# NP-100v12_cam.net
KiCad netlist of a schematic drawn in EAGLE
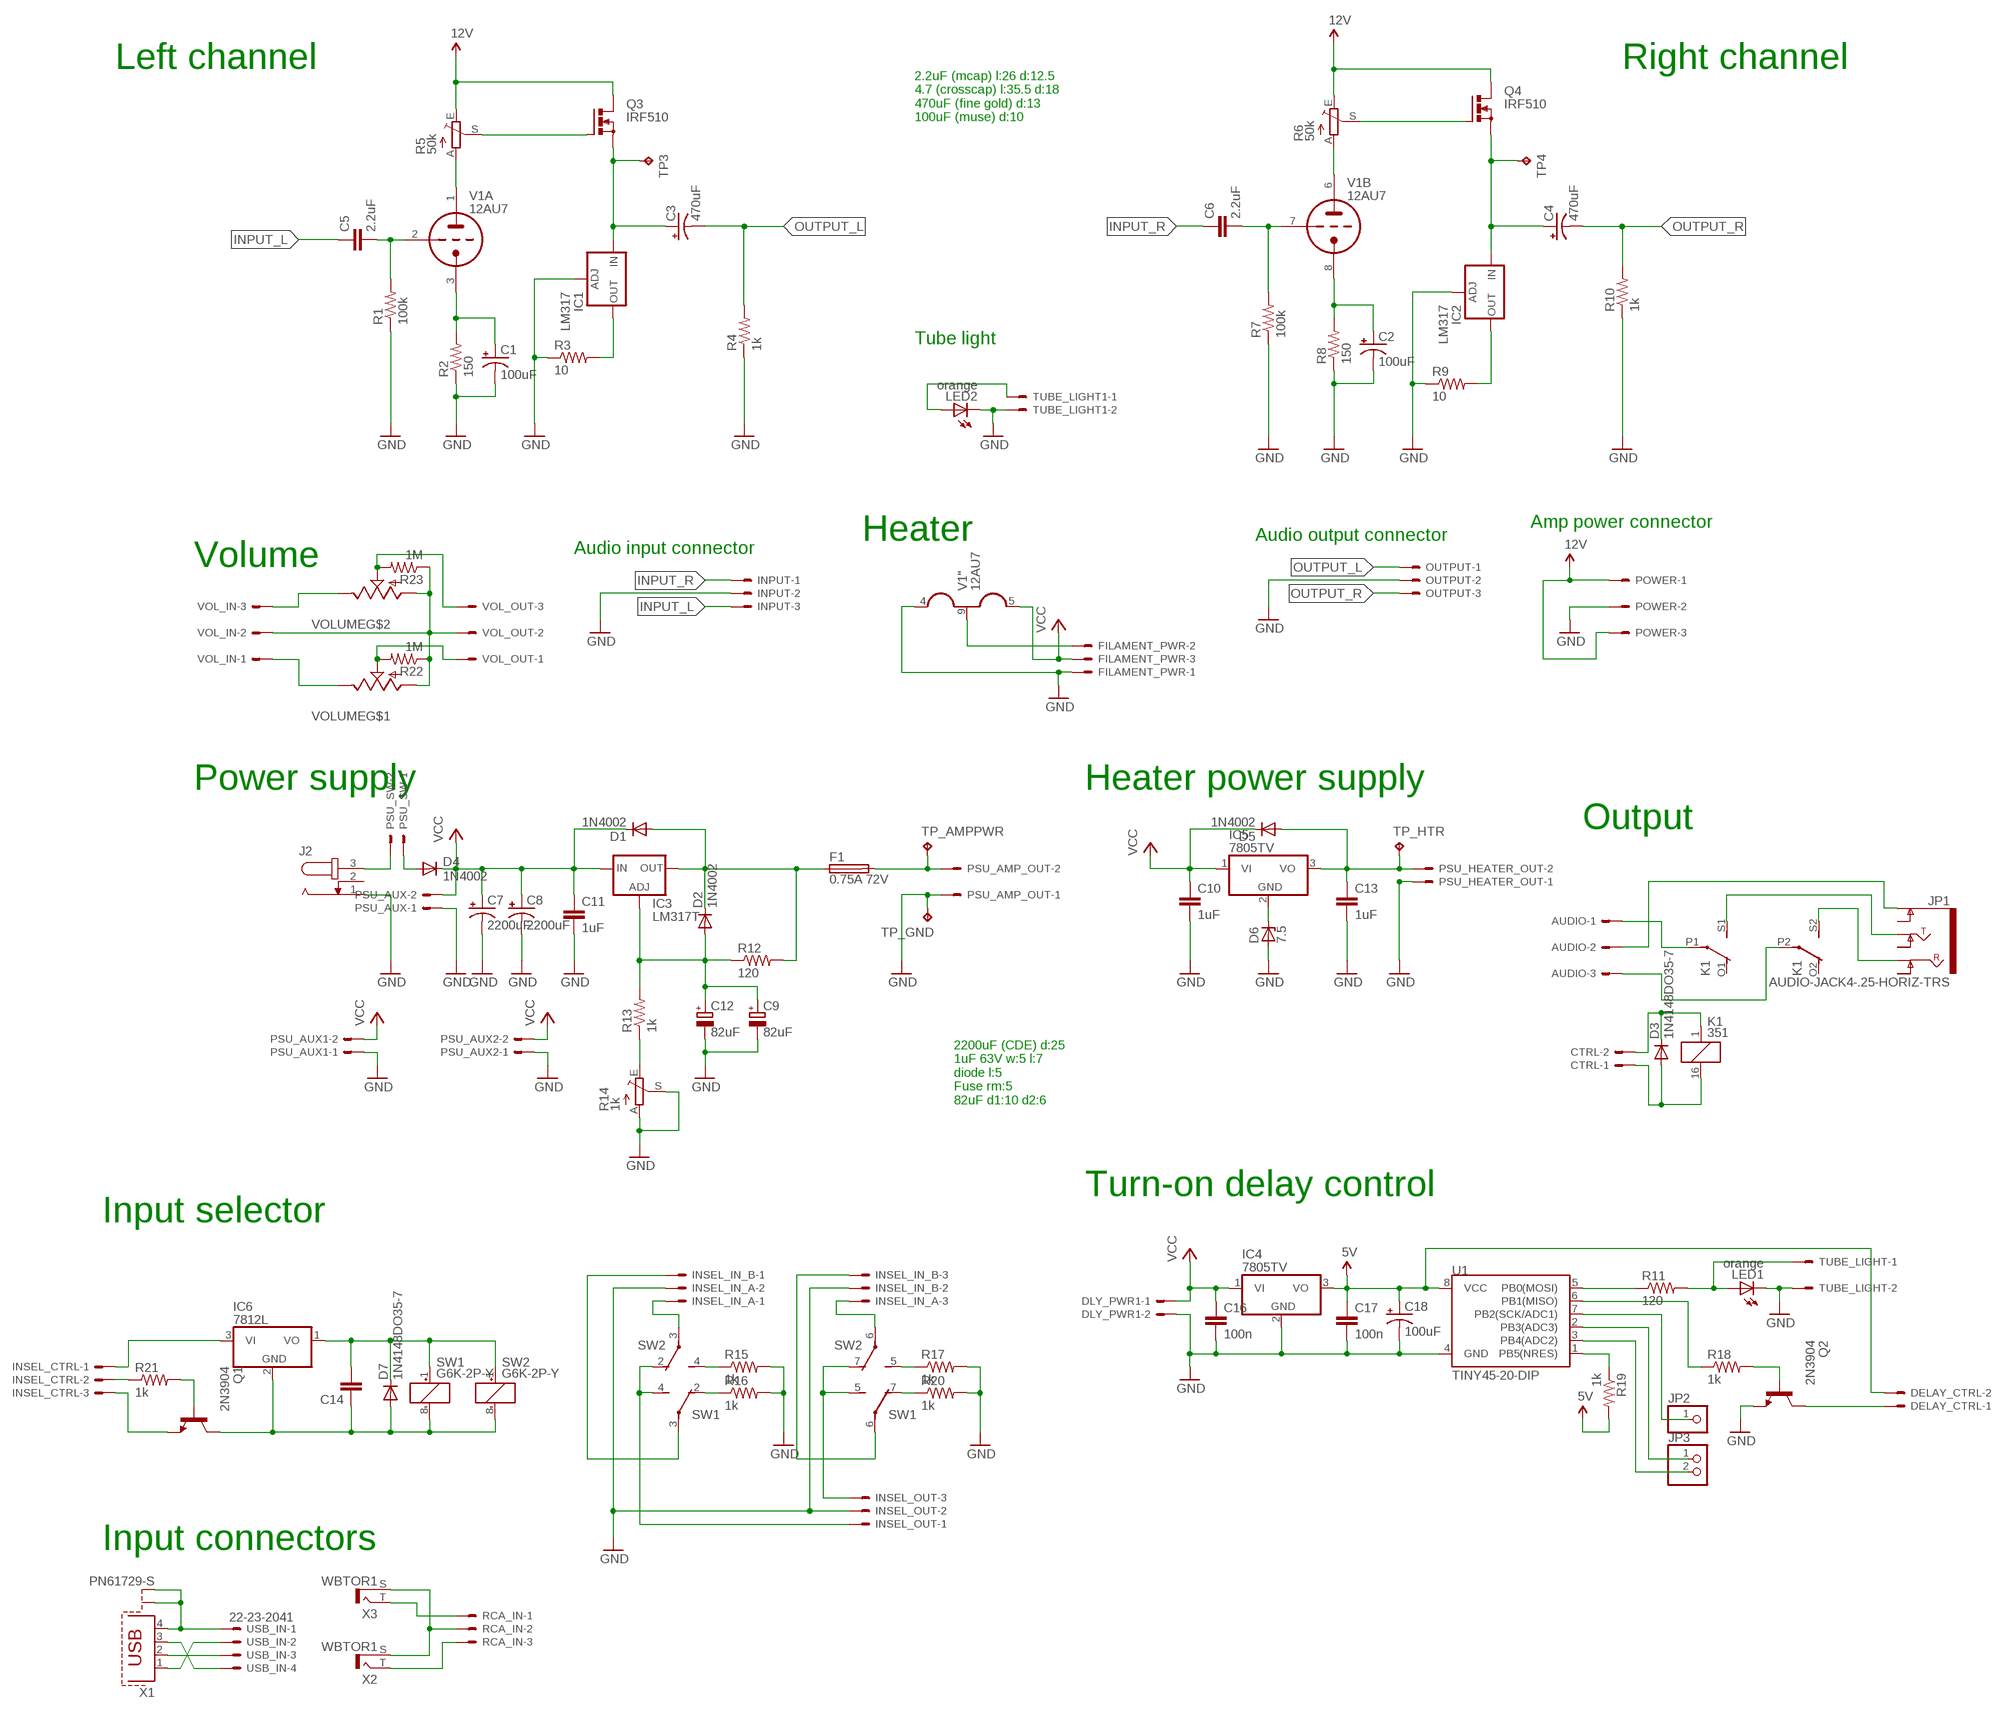
[diagram p0: schematic, sheet 1]

(export (version "E")
  (design (tool "Eeschema 10.0.6"))
  (components
    (comp (ref "AUDIO")
      (value "22-23-2031")
      (footprint "eagle-import:22-23-2031")
      (fields (field (name "MF") "MOLEX"))
      (libsource (lib "eagle-import") (part "22-23-2031"))
    )
    (comp (ref "C1")
      (value "100uF")
      (footprint "eagle-import:E5-10,5")
      (libsource (lib "eagle-import") (part "CPOL-USE5-10.5"))
    )
    (comp (ref "C2")
      (value "100uF")
      (footprint "eagle-import:E5-10,5")
      (libsource (lib "eagle-import") (part "CPOL-USE5-10.5"))
    )
    (comp (ref "C3")
      (value "470uF")
      (footprint "eagle-import:E5-13")
      (libsource (lib "eagle-import") (part "CPOL-USE5-13"))
    )
    (comp (ref "C4")
      (value "470uF")
      (footprint "eagle-import:E5-13")
      (libsource (lib "eagle-import") (part "CPOL-USE5-13"))
    )
    (comp (ref "C5")
      (value "2.2uF")
      (footprint "eagle-import:C37.5B19")
      (libsource (lib "eagle-import") (part "C37/19"))
    )
    (comp (ref "C6")
      (value "2.2uF")
      (footprint "eagle-import:C37.5B19")
      (libsource (lib "eagle-import") (part "C37/19"))
    )
    (comp (ref "C7")
      (value "2200uF")
      (footprint "eagle-import:EB25D")
      (libsource (lib "eagle-import") (part "CPOL-USE10-25"))
    )
    (comp (ref "C8")
      (value "2200uF")
      (footprint "eagle-import:EB25D")
      (libsource (lib "eagle-import") (part "CPOL-USE10-25"))
    )
    (comp (ref "C9")
      (value "82uF")
      (footprint "eagle-import:E2,5-6")
      (libsource (lib "eagle-import") (part "CPOL-EUE2.5-6"))
    )
    (comp (ref "C10")
      (value "1uF")
      (footprint "eagle-import:C5B4.5")
      (libsource (lib "eagle-import") (part "C5/4.5"))
    )
    (comp (ref "C11")
      (value "1uF")
      (footprint "eagle-import:C5B4.5")
      (libsource (lib "eagle-import") (part "C5/4.5"))
    )
    (comp (ref "C12")
      (value "82uF")
      (footprint "eagle-import:E5-10,5")
      (libsource (lib "eagle-import") (part "CPOL-EUE5-10.5"))
    )
    (comp (ref "C13")
      (value "1uF")
      (footprint "eagle-import:C5B4.5")
      (libsource (lib "eagle-import") (part "C5/4.5"))
    )
    (comp (ref "C14")
      (value "C5/2.5")
      (footprint "eagle-import:C5B2.5")
      (libsource (lib "eagle-import") (part "C5/2.5"))
    )
    (comp (ref "C16")
      (value "100n")
      (footprint "eagle-import:CAP-PTH-5MM")
      (libsource (lib "eagle-import") (part "CAPPTH1"))
    )
    (comp (ref "C17")
      (value "100n")
      (footprint "eagle-import:CAP-PTH-5MM")
      (libsource (lib "eagle-import") (part "CAPPTH1"))
    )
    (comp (ref "C18")
      (value "100uF")
      (footprint "eagle-import:E2,5-7")
      (libsource (lib "eagle-import") (part "CPOL-USE2.5-7"))
    )
    (comp (ref "CTRL")
      (value "22-23-2021")
      (footprint "eagle-import:22-23-2021")
      (fields (field (name "MF") "MOLEX"))
      (libsource (lib "eagle-import") (part "22-23-2021"))
    )
    (comp (ref "D1")
      (value "1N4002")
      (footprint "eagle-import:D-7.5")
      (libsource (lib "eagle-import") (part "DIODE-D-7.5"))
    )
    (comp (ref "D2")
      (value "1N4002")
      (footprint "eagle-import:D-7.5")
      (libsource (lib "eagle-import") (part "DIODE-D-7.5"))
    )
    (comp (ref "D3")
      (value "1N4148DO35-7")
      (footprint "eagle-import:DO35-7")
      (libsource (lib "eagle-import") (part "1N4148DO35-7"))
    )
    (comp (ref "D4")
      (value "1N4002")
      (footprint "eagle-import:D-5")
      (libsource (lib "eagle-import") (part "DIODE-D-5"))
    )
    (comp (ref "D5")
      (value "1N4002")
      (footprint "eagle-import:D-7.5")
      (libsource (lib "eagle-import") (part "DIODE-D-7.5"))
    )
    (comp (ref "D6")
      (value "7.5")
      (footprint "eagle-import:DO34Z7")
      (libsource (lib "eagle-import") (part "ZENER-DIODEDO34-7"))
    )
    (comp (ref "D7")
      (value "1N4148DO35-7")
      (footprint "eagle-import:DO35-7")
      (libsource (lib "eagle-import") (part "1N4148DO35-7"))
    )
    (comp (ref "DELAY_CTRL")
      (value "22-23-2021")
      (footprint "eagle-import:22-23-2021")
      (fields (field (name "MF") "MOLEX"))
      (libsource (lib "eagle-import") (part "22-23-2021"))
    )
    (comp (ref "DLY_PWR1")
      (value "22-23-2021")
      (footprint "eagle-import:22-23-2021")
      (fields (field (name "MF") "MOLEX"))
      (libsource (lib "eagle-import") (part "22-23-2021"))
    )
    (comp (ref "F1")
      (value "0.75A 72V")
      (footprint "eagle-import:TE5")
      (libsource (lib "eagle-import") (part "TE5"))
    )
    (comp (ref "FILAMENT_PWR")
      (value "22-23-2031")
      (footprint "eagle-import:22-23-2031")
      (fields (field (name "MF") "MOLEX"))
      (libsource (lib "eagle-import") (part "22-23-2031"))
    )
    (comp (ref "IC1")
      (value "LM317")
      (footprint "eagle-import:317TS")
      (libsource (lib "eagle-import") (part "LM317TS"))
    )
    (comp (ref "IC2")
      (value "LM317")
      (footprint "eagle-import:317TS")
      (libsource (lib "eagle-import") (part "LM317TS"))
    )
    (comp (ref "IC3")
      (value "LM317T")
      (footprint "eagle-import:317TS")
      (libsource (lib "eagle-import") (part "LM317TS"))
    )
    (comp (ref "IC4")
      (value "7805TV")
      (footprint "eagle-import:TO220V")
      (libsource (lib "eagle-import") (part "78TV05"))
    )
    (comp (ref "IC5")
      (value "7805TV")
      (footprint "eagle-import:TO220V")
      (libsource (lib "eagle-import") (part "78TV05"))
    )
    (comp (ref "IC6")
      (value "7812L")
      (footprint "eagle-import:TO92")
      (libsource (lib "eagle-import") (part "78L12"))
    )
    (comp (ref "INPUT")
      (value "22-23-2031")
      (footprint "eagle-import:22-23-2031")
      (fields (field (name "MF") "MOLEX"))
      (libsource (lib "eagle-import") (part "22-23-2031"))
    )
    (comp (ref "INSEL_CTRL")
      (value "22-23-2031")
      (footprint "eagle-import:22-23-2031")
      (fields (field (name "MF") "MOLEX"))
      (libsource (lib "eagle-import") (part "22-23-2031"))
    )
    (comp (ref "INSEL_IN_A")
      (value "22-23-2031")
      (footprint "eagle-import:22-23-2031")
      (fields (field (name "MF") "MOLEX"))
      (libsource (lib "eagle-import") (part "22-23-2031"))
    )
    (comp (ref "INSEL_IN_B")
      (value "22-23-2031")
      (footprint "eagle-import:22-23-2031")
      (fields (field (name "MF") "MOLEX"))
      (libsource (lib "eagle-import") (part "22-23-2031"))
    )
    (comp (ref "INSEL_OUT")
      (value "22-23-2031")
      (footprint "eagle-import:22-23-2031")
      (fields (field (name "MF") "MOLEX"))
      (libsource (lib "eagle-import") (part "22-23-2031"))
    )
    (comp (ref "J2")
      (value "JACK-PLUG0")
      (footprint "eagle-import:SPC4077")
      (libsource (lib "eagle-import") (part "JACK-PLUG0"))
    )
    (comp (ref "JP1")
      (value "AUDIO-JACK4-.25-HORIZ-TRS")
      (footprint "eagle-import:AUDIO-JACK-.25-INCH-HORIZ-PTH")
      (libsource (lib "eagle-import") (part "AUDIO-JACK4-.25-HORIZ-TRS"))
    )
    (comp (ref "JP2")
      (value "PINHD-1X1")
      (footprint "eagle-import:1X01")
      (libsource (lib "eagle-import") (part "PINHD-1X1"))
    )
    (comp (ref "JP3")
      (value "PINHD-1X2")
      (footprint "eagle-import:1X02")
      (libsource (lib "eagle-import") (part "PINHD-1X2"))
    )
    (comp (ref "K1")
      (value "351")
      (footprint "eagle-import:351")
      (libsource (lib "eagle-import") (part "351"))
    )
    (comp (ref "LED1")
      (value "orange")
      (footprint "eagle-import:LED3MM")
      (libsource (lib "eagle-import") (part "LED3MM"))
    )
    (comp (ref "LED2")
      (value "orange")
      (footprint "eagle-import:LED3MM")
      (libsource (lib "eagle-import") (part "LED3MM"))
    )
    (comp (ref "OUTPUT")
      (value "22-23-2031")
      (footprint "eagle-import:22-23-2031")
      (fields (field (name "MF") "MOLEX"))
      (libsource (lib "eagle-import") (part "22-23-2031"))
    )
    (comp (ref "POWER")
      (value "22-23-2031")
      (footprint "eagle-import:22-23-2031")
      (fields (field (name "MF") "MOLEX"))
      (libsource (lib "eagle-import") (part "22-23-2031"))
    )
    (comp (ref "PSU_AMP_OUT")
      (value "22-23-2021")
      (footprint "eagle-import:22-23-2021")
      (fields (field (name "MF") "MOLEX"))
      (libsource (lib "eagle-import") (part "22-23-2021"))
    )
    (comp (ref "PSU_AUX")
      (value "22-23-2021")
      (footprint "eagle-import:22-23-2021")
      (fields (field (name "MF") "MOLEX"))
      (libsource (lib "eagle-import") (part "22-23-2021"))
    )
    (comp (ref "PSU_AUX1")
      (value "22-23-2021")
      (footprint "eagle-import:22-23-2021")
      (fields (field (name "MF") "MOLEX"))
      (libsource (lib "eagle-import") (part "22-23-2021"))
    )
    (comp (ref "PSU_AUX2")
      (value "22-23-2021")
      (footprint "eagle-import:22-23-2021")
      (fields (field (name "MF") "MOLEX"))
      (libsource (lib "eagle-import") (part "22-23-2021"))
    )
    (comp (ref "PSU_HEATER_OUT")
      (value "22-23-2021")
      (footprint "eagle-import:22-23-2021")
      (fields (field (name "MF") "MOLEX"))
      (libsource (lib "eagle-import") (part "22-23-2021"))
    )
    (comp (ref "PSU_SW")
      (value "22-23-2021")
      (footprint "eagle-import:22-23-2021")
      (fields (field (name "MF") "MOLEX"))
      (libsource (lib "eagle-import") (part "22-23-2021"))
    )
    (comp (ref "Q1")
      (value "2N3904")
      (footprint "eagle-import:TO92")
      (libsource (lib "eagle-import") (part "2N3904"))
    )
    (comp (ref "Q2")
      (value "2N3904")
      (footprint "eagle-import:TO92")
      (libsource (lib "eagle-import") (part "2N3904"))
    )
    (comp (ref "Q3")
      (value "IRF510")
      (footprint "eagle-import:TO220BV")
      (libsource (lib "eagle-import") (part "PMOSFET_NTO220BV"))
    )
    (comp (ref "Q4")
      (value "IRF510")
      (footprint "eagle-import:TO220BV")
      (libsource (lib "eagle-import") (part "PMOSFET_NTO220BV"))
    )
    (comp (ref "R1")
      (value "100k")
      (footprint "eagle-import:0207_10")
      (libsource (lib "eagle-import") (part "R-US_0207/10"))
    )
    (comp (ref "R2")
      (value "150")
      (footprint "eagle-import:0207_10")
      (libsource (lib "eagle-import") (part "R-US_0207/10"))
    )
    (comp (ref "R3")
      (value "10")
      (footprint "eagle-import:0207_10")
      (libsource (lib "eagle-import") (part "R-US_0207/10"))
    )
    (comp (ref "R4")
      (value "1k")
      (footprint "eagle-import:0207_10")
      (libsource (lib "eagle-import") (part "R-US_0207/10"))
    )
    (comp (ref "R5")
      (value "50k")
      (footprint "eagle-import:SP19L")
      (libsource (lib "eagle-import") (part "TRIM_EU-B90P"))
    )
    (comp (ref "R6")
      (value "50k")
      (footprint "eagle-import:SP19L")
      (libsource (lib "eagle-import") (part "TRIM_EU-B90P"))
    )
    (comp (ref "R7")
      (value "100k")
      (footprint "eagle-import:0207_10")
      (libsource (lib "eagle-import") (part "R-US_0207/10"))
    )
    (comp (ref "R8")
      (value "150")
      (footprint "eagle-import:0207_10")
      (libsource (lib "eagle-import") (part "R-US_0207/10"))
    )
    (comp (ref "R9")
      (value "10")
      (footprint "eagle-import:0207_10")
      (libsource (lib "eagle-import") (part "R-US_0207/10"))
    )
    (comp (ref "R10")
      (value "1k")
      (footprint "eagle-import:0207_10")
      (libsource (lib "eagle-import") (part "R-US_0207/10"))
    )
    (comp (ref "R11")
      (value "120")
      (footprint "eagle-import:0204_7")
      (libsource (lib "eagle-import") (part "R-US_0204/7"))
    )
    (comp (ref "R12")
      (value "120")
      (footprint "eagle-import:AXIAL-0.3")
      (libsource (lib "eagle-import") (part "RESISTORAXIAL-0.3"))
    )
    (comp (ref "R13")
      (value "1k")
      (footprint "eagle-import:AXIAL-0.3")
      (libsource (lib "eagle-import") (part "RESISTORAXIAL-0.3"))
    )
    (comp (ref "R14")
      (value "1k")
      (footprint "eagle-import:S64Y")
      (libsource (lib "eagle-import") (part "TRIM_EU-S64Y"))
    )
    (comp (ref "R15")
      (value "1k")
      (footprint "eagle-import:AXIAL-0.3")
      (libsource (lib "eagle-import") (part "RESISTORAXIAL-0.3"))
    )
    (comp (ref "R16")
      (value "1k")
      (footprint "eagle-import:AXIAL-0.3")
      (libsource (lib "eagle-import") (part "RESISTORAXIAL-0.3"))
    )
    (comp (ref "R17")
      (value "1k")
      (footprint "eagle-import:AXIAL-0.3")
      (libsource (lib "eagle-import") (part "RESISTORAXIAL-0.3"))
    )
    (comp (ref "R18")
      (value "1k")
      (footprint "eagle-import:0204_7")
      (libsource (lib "eagle-import") (part "R-US_0204/7"))
    )
    (comp (ref "R19")
      (value "1k")
      (footprint "eagle-import:0204_7")
      (libsource (lib "eagle-import") (part "R-US_0204/7"))
    )
    (comp (ref "R20")
      (value "1k")
      (footprint "eagle-import:AXIAL-0.3")
      (libsource (lib "eagle-import") (part "RESISTORAXIAL-0.3"))
    )
    (comp (ref "R21")
      (value "1k")
      (footprint "eagle-import:0204_7")
      (libsource (lib "eagle-import") (part "R-US_0204/7"))
    )
    (comp (ref "R22")
      (value "1M")
      (footprint "eagle-import:0207_10")
      (libsource (lib "eagle-import") (part "R-US_0207/10"))
    )
    (comp (ref "R23")
      (value "1M")
      (footprint "eagle-import:0207_10")
      (libsource (lib "eagle-import") (part "R-US_0207/10"))
    )
    (comp (ref "RCA_IN")
      (value "22-23-2031")
      (footprint "eagle-import:22-23-2031")
      (fields (field (name "MF") "MOLEX"))
      (libsource (lib "eagle-import") (part "22-23-2031"))
    )
    (comp (ref "SW1")
      (value "G6K-2P-Y")
      (footprint "eagle-import:G6K-2P-Y")
      (fields (field (name "MF") "OMRON COMPONENTS USA") (field (name "MPN") "G6K-2P-Y DC12"))
      (libsource (lib "eagle-import") (part "G6K-2P-Y"))
    )
    (comp (ref "SW2")
      (value "G6K-2P-Y")
      (footprint "eagle-import:G6K-2P-Y")
      (fields (field (name "MF") "OMRON COMPONENTS USA") (field (name "MPN") "G6K-2P-Y DC12"))
      (libsource (lib "eagle-import") (part "G6K-2P-Y"))
    )
    (comp (ref "TP3")
      (value "TPPAD1-17")
      (footprint "eagle-import:P1-17")
      (libsource (lib "eagle-import") (part "TPPAD1-17"))
    )
    (comp (ref "TP4")
      (value "TPPAD1-17")
      (footprint "eagle-import:P1-17")
      (libsource (lib "eagle-import") (part "TPPAD1-17"))
    )
    (comp (ref "TP_AMPPWR")
      (value "TPPAD1-17")
      (footprint "eagle-import:P1-17")
      (libsource (lib "eagle-import") (part "TPPAD1-17"))
    )
    (comp (ref "TP_GND")
      (value "TPPAD1-17")
      (footprint "eagle-import:P1-17")
      (libsource (lib "eagle-import") (part "TPPAD1-17"))
    )
    (comp (ref "TP_HTR")
      (value "TPPAD1-17")
      (footprint "eagle-import:P1-17")
      (libsource (lib "eagle-import") (part "TPPAD1-17"))
    )
    (comp (ref "TUBE_LIGHT")
      (value "22-23-2021")
      (footprint "eagle-import:22-23-2021")
      (fields (field (name "MF") "MOLEX"))
      (libsource (lib "eagle-import") (part "22-23-2021"))
    )
    (comp (ref "TUBE_LIGHT1")
      (value "22-23-2021")
      (footprint "eagle-import:22-23-2021")
      (fields (field (name "MF") "MOLEX"))
      (libsource (lib "eagle-import") (part "22-23-2021"))
    )
    (comp (ref "U1")
      (value "TINY45-20-DIP")
      (footprint "eagle-import:DIP08")
      (libsource (lib "eagle-import") (part "ATTINY45TINY45-20-DIP"))
    )
    (comp (ref "USB_IN")
      (value "22-23-2041")
      (footprint "eagle-import:22-23-2041")
      (fields (field (name "MF") "MOLEX"))
      (libsource (lib "eagle-import") (part "22-23-2041"))
    )
    (comp (ref "V1")
      (value "12AU7")
      (footprint "eagle-import:NOVAL")
      (libsource (lib "eagle-import") (part "12AU7-P"))
    )
    (comp (ref "VOLUME")
      (value "ALPS_BLUE")
      (footprint "eagle-import:ALPS_RK27")
      (libsource (lib "eagle-import") (part "ALPS_BLUE"))
    )
    (comp (ref "VOL_IN")
      (value "22-23-2031")
      (footprint "eagle-import:22-23-2031")
      (fields (field (name "MF") "MOLEX"))
      (libsource (lib "eagle-import") (part "22-23-2031"))
    )
    (comp (ref "VOL_OUT")
      (value "22-23-2031")
      (footprint "eagle-import:22-23-2031")
      (fields (field (name "MF") "MOLEX"))
      (libsource (lib "eagle-import") (part "22-23-2031"))
    )
    (comp (ref "X1")
      (value "PN61729-S")
      (footprint "eagle-import:PN61729-S")
      (libsource (lib "eagle-import") (part "PN61729-S"))
    )
    (comp (ref "X2")
      (value "WBTOR1")
      (footprint "eagle-import:WBTOR1")
      (fields (field (name "MPN") "WBTOR 1 BLACK"))
      (libsource (lib "eagle-import") (part "WBTOR1"))
    )
    (comp (ref "X3")
      (value "WBTOR1")
      (footprint "eagle-import:WBTOR1")
      (fields (field (name "MPN") "WBTOR 1 BLACK"))
      (libsource (lib "eagle-import") (part "WBTOR1"))
    )
  )
  (nets
    (net (code "1") (name "5V") (class "Default")
      (node (ref "C17") (pin "1") (pinfunction "1_1") (pintype "passive"))
      (node (ref "C18") (pin "+") (pinfunction "+_+") (pintype "passive"))
      (node (ref "DELAY_CTRL") (pin "2") (pinfunction "S_2") (pintype "passive"))
      (node (ref "IC4") (pin "3") (pinfunction "VO_3") (pintype "passive"))
      (node (ref "R19") (pin "2") (pinfunction "2_2") (pintype "passive"))
      (node (ref "U1") (pin "8") (pinfunction "VCC_8") (pintype "bidirectional"))
    )
    (net (code "2") (name "12V") (class "Default")
      (node (ref "POWER") (pin "1") (pinfunction "S_1") (pintype "passive"))
      (node (ref "POWER") (pin "3") (pinfunction "S_3") (pintype "passive"))
      (node (ref "Q3") (pin "D") (pinfunction "D_D") (pintype "passive"))
      (node (ref "Q4") (pin "D") (pinfunction "D_D") (pintype "passive"))
      (node (ref "R5") (pin "E") (pinfunction "E_E") (pintype "passive"))
      (node (ref "R6") (pin "E") (pinfunction "E_E") (pintype "passive"))
    )
    (net (code "3") (name "GND") (class "Default")
      (node (ref "C1") (pin "-") (pinfunction "-_-") (pintype "passive"))
      (node (ref "C10") (pin "2") (pinfunction "2_2") (pintype "passive"))
      (node (ref "C11") (pin "2") (pinfunction "2_2") (pintype "passive"))
      (node (ref "C12") (pin "-") (pinfunction "-_-") (pintype "passive"))
      (node (ref "C13") (pin "2") (pinfunction "2_2") (pintype "passive"))
      (node (ref "C16") (pin "2") (pinfunction "2_2") (pintype "passive"))
      (node (ref "C17") (pin "2") (pinfunction "2_2") (pintype "passive"))
      (node (ref "C18") (pin "-") (pinfunction "-_-") (pintype "passive"))
      (node (ref "C2") (pin "-") (pinfunction "-_-") (pintype "passive"))
      (node (ref "C7") (pin "-") (pinfunction "-_-") (pintype "passive"))
      (node (ref "C8") (pin "-") (pinfunction "-_-") (pintype "passive"))
      (node (ref "C9") (pin "-") (pinfunction "-_-") (pintype "passive"))
      (node (ref "D6") (pin "A") (pinfunction "A_A") (pintype "passive"))
      (node (ref "DLY_PWR1") (pin "2") (pinfunction "S_2") (pintype "passive"))
      (node (ref "FILAMENT_PWR") (pin "1") (pinfunction "S_1") (pintype "passive"))
      (node (ref "IC1") (pin "1") (pinfunction "ADJ_1") (pintype "input"))
      (node (ref "IC2") (pin "1") (pinfunction "ADJ_1") (pintype "input"))
      (node (ref "IC4") (pin "2") (pinfunction "GND_2") (pintype "passive"))
      (node (ref "INPUT") (pin "2") (pinfunction "S_2") (pintype "passive"))
      (node (ref "INSEL_IN_A") (pin "2") (pinfunction "S_2") (pintype "passive"))
      (node (ref "INSEL_IN_B") (pin "2") (pinfunction "S_2") (pintype "passive"))
      (node (ref "INSEL_OUT") (pin "2") (pinfunction "S_2") (pintype "passive"))
      (node (ref "J2") (pin "1") (pinfunction "1_1") (pintype "passive"))
      (node (ref "LED1") (pin "K") (pinfunction "C_K") (pintype "passive"))
      (node (ref "LED2") (pin "K") (pinfunction "C_K") (pintype "passive"))
      (node (ref "OUTPUT") (pin "2") (pinfunction "S_2") (pintype "passive"))
      (node (ref "POWER") (pin "2") (pinfunction "S_2") (pintype "passive"))
      (node (ref "PSU_AMP_OUT") (pin "1") (pinfunction "S_1") (pintype "passive"))
      (node (ref "PSU_AUX") (pin "1") (pinfunction "S_1") (pintype "passive"))
      (node (ref "PSU_AUX1") (pin "1") (pinfunction "S_1") (pintype "passive"))
      (node (ref "PSU_AUX2") (pin "1") (pinfunction "S_1") (pintype "passive"))
      (node (ref "PSU_HEATER_OUT") (pin "1") (pinfunction "S_1") (pintype "passive"))
      (node (ref "Q2") (pin "3") (pinfunction "E_3") (pintype "passive"))
      (node (ref "R1") (pin "1") (pinfunction "1_1") (pintype "passive"))
      (node (ref "R10") (pin "1") (pinfunction "1_1") (pintype "passive"))
      (node (ref "R14") (pin "A") (pinfunction "A_A") (pintype "passive"))
      (node (ref "R14") (pin "S") (pinfunction "S_S") (pintype "passive"))
      (node (ref "R15") (pin "P$2") (pinfunction "2_P$2") (pintype "passive"))
      (node (ref "R16") (pin "P$2") (pinfunction "2_P$2") (pintype "passive"))
      (node (ref "R17") (pin "P$2") (pinfunction "2_P$2") (pintype "passive"))
      (node (ref "R2") (pin "1") (pinfunction "1_1") (pintype "passive"))
      (node (ref "R20") (pin "P$2") (pinfunction "2_P$2") (pintype "passive"))
      (node (ref "R3") (pin "1") (pinfunction "1_1") (pintype "passive"))
      (node (ref "R4") (pin "1") (pinfunction "1_1") (pintype "passive"))
      (node (ref "R7") (pin "1") (pinfunction "1_1") (pintype "passive"))
      (node (ref "R8") (pin "1") (pinfunction "1_1") (pintype "passive"))
      (node (ref "R9") (pin "1") (pinfunction "1_1") (pintype "passive"))
      (node (ref "TP_GND") (pin "TP") (pinfunction "TP_TP") (pintype "input"))
      (node (ref "TUBE_LIGHT") (pin "2") (pinfunction "S_2") (pintype "passive"))
      (node (ref "TUBE_LIGHT1") (pin "2") (pinfunction "S_2") (pintype "passive"))
      (node (ref "U1") (pin "4") (pinfunction "GND_4") (pintype "bidirectional"))
      (node (ref "V1") (pin "4") (pinfunction "H1_4") (pintype "passive"))
    )
    (net (code "4") (name "INPUT_L") (class "Default")
      (node (ref "C5") (pin "1") (pinfunction "1_1") (pintype "passive"))
      (node (ref "INPUT") (pin "3") (pinfunction "S_3") (pintype "passive"))
    )
    (net (code "5") (name "INPUT_R") (class "Default")
      (node (ref "C6") (pin "1") (pinfunction "1_1") (pintype "passive"))
      (node (ref "INPUT") (pin "1") (pinfunction "S_1") (pintype "passive"))
    )
    (net (code "6") (name "Net-(AUDIOA-S)") (class "Default")
      (node (ref "AUDIO") (pin "1") (pinfunction "S_1") (pintype "passive"))
      (node (ref "K1") (pin "P1") (pinfunction "P_P1") (pintype "passive"))
    )
    (net (code "7") (name "Net-(AUDIOB-S)") (class "Default")
      (node (ref "AUDIO") (pin "2") (pinfunction "S_2") (pintype "passive"))
      (node (ref "JP1") (pin "SLEEVE") (pinfunction "EARTH_SLEEVE") (pintype "bidirectional"))
    )
    (net (code "8") (name "Net-(AUDIOC-S)") (class "Default")
      (node (ref "AUDIO") (pin "3") (pinfunction "S_3") (pintype "passive"))
      (node (ref "K1") (pin "P2") (pinfunction "P_P2") (pintype "passive"))
    )
    (net (code "9") (name "Net-(CTRLA-S)") (class "Default")
      (node (ref "CTRL") (pin "1") (pinfunction "S_1") (pintype "passive"))
      (node (ref "D3") (pin "A") (pinfunction "A_A") (pintype "passive"))
      (node (ref "K1") (pin "16") (pinfunction "2_16") (pintype "passive"))
    )
    (net (code "10") (name "Net-(CTRLB-S)") (class "Default")
      (node (ref "CTRL") (pin "2") (pinfunction "S_2") (pintype "passive"))
      (node (ref "D3") (pin "C") (pinfunction "C_C") (pintype "passive"))
      (node (ref "K1") (pin "1") (pinfunction "1_1") (pintype "passive"))
    )
    (net (code "11") (name "Net-(DELAY_CTRLA-S)") (class "Default")
      (node (ref "DELAY_CTRL") (pin "1") (pinfunction "S_1") (pintype "passive"))
      (node (ref "Q2") (pin "1") (pinfunction "C_1") (pintype "passive"))
    )
    (net (code "12") (name "Net-(FILAMENT_PWRB-S)") (class "Default")
      (node (ref "FILAMENT_PWR") (pin "2") (pinfunction "S_2") (pintype "passive"))
      (node (ref "V1") (pin "9") (pinfunction "H2_9") (pintype "passive"))
    )
    (net (code "13") (name "Net-(IC1-IN)") (class "Default")
      (node (ref "C3") (pin "+") (pinfunction "+_+") (pintype "passive"))
      (node (ref "IC1") (pin "3") (pinfunction "IN_3") (pintype "input"))
      (node (ref "Q3") (pin "S") (pinfunction "S_S") (pintype "passive"))
      (node (ref "TP3") (pin "TP") (pinfunction "TP_TP") (pintype "input"))
    )
    (net (code "14") (name "Net-(IC1-OUT)") (class "Default")
      (node (ref "IC1") (pin "2") (pinfunction "OUT_2") (pintype "passive"))
      (node (ref "R3") (pin "2") (pinfunction "2_2") (pintype "passive"))
    )
    (net (code "15") (name "Net-(IC2-IN)") (class "Default")
      (node (ref "C4") (pin "+") (pinfunction "+_+") (pintype "passive"))
      (node (ref "IC2") (pin "3") (pinfunction "IN_3") (pintype "input"))
      (node (ref "Q4") (pin "S") (pinfunction "S_S") (pintype "passive"))
      (node (ref "TP4") (pin "TP") (pinfunction "TP_TP") (pintype "input"))
    )
    (net (code "16") (name "Net-(IC2-OUT)") (class "Default")
      (node (ref "IC2") (pin "2") (pinfunction "OUT_2") (pintype "passive"))
      (node (ref "R9") (pin "2") (pinfunction "2_2") (pintype "passive"))
    )
    (net (code "17") (name "Net-(IC3-ADJ)") (class "Default")
      (node (ref "C12") (pin "+") (pinfunction "+_+") (pintype "passive"))
      (node (ref "C9") (pin "+") (pinfunction "+_+") (pintype "passive"))
      (node (ref "D2") (pin "A") (pinfunction "A_A") (pintype "passive"))
      (node (ref "IC3") (pin "1") (pinfunction "ADJ_1") (pintype "input"))
      (node (ref "R12") (pin "P$1") (pinfunction "1_P$1") (pintype "passive"))
      (node (ref "R13") (pin "P$2") (pinfunction "2_P$2") (pintype "passive"))
    )
    (net (code "18") (name "Net-(IC3-OUT)") (class "Default")
      (node (ref "D1") (pin "A") (pinfunction "A_A") (pintype "passive"))
      (node (ref "D2") (pin "C") (pinfunction "C_C") (pintype "passive"))
      (node (ref "F1") (pin "1") (pinfunction "1_1") (pintype "passive"))
      (node (ref "IC3") (pin "2") (pinfunction "OUT_2") (pintype "passive"))
      (node (ref "R12") (pin "P$2") (pinfunction "2_P$2") (pintype "passive"))
    )
    (net (code "19") (name "Net-(IC5-GND)") (class "Default")
      (node (ref "D6") (pin "C") (pinfunction "C_C") (pintype "passive"))
      (node (ref "IC5") (pin "2") (pinfunction "GND_2") (pintype "passive"))
    )
    (net (code "20") (name "Net-(IC5-VO)") (class "Default")
      (node (ref "C13") (pin "1") (pinfunction "1_1") (pintype "passive"))
      (node (ref "D5") (pin "A") (pinfunction "A_A") (pintype "passive"))
      (node (ref "IC5") (pin "3") (pinfunction "VO_3") (pintype "passive"))
      (node (ref "PSU_HEATER_OUT") (pin "2") (pinfunction "S_2") (pintype "passive"))
      (node (ref "TP_HTR") (pin "TP") (pinfunction "TP_TP") (pintype "input"))
    )
    (net (code "21") (name "Net-(IC6-GND)") (class "Default")
      (node (ref "C14") (pin "1") (pinfunction "1_1") (pintype "passive"))
      (node (ref "D7") (pin "A") (pinfunction "A_A") (pintype "passive"))
      (node (ref "IC6") (pin "2") (pinfunction "GND_2") (pintype "passive"))
      (node (ref "Q1") (pin "1") (pinfunction "C_1") (pintype "passive"))
      (node (ref "SW1") (pin "8") (pinfunction "-_8") (pintype "passive"))
      (node (ref "SW2") (pin "8") (pinfunction "-_8") (pintype "passive"))
    )
    (net (code "22") (name "Net-(IC6-VI)") (class "Default")
      (node (ref "IC6") (pin "3") (pinfunction "VI_3") (pintype "input"))
      (node (ref "INSEL_CTRL") (pin "1") (pinfunction "S_1") (pintype "passive"))
    )
    (net (code "23") (name "Net-(IC6-VO)") (class "Default")
      (node (ref "C14") (pin "2") (pinfunction "2_2") (pintype "passive"))
      (node (ref "D7") (pin "C") (pinfunction "C_C") (pintype "passive"))
      (node (ref "IC6") (pin "1") (pinfunction "VO_1") (pintype "passive"))
      (node (ref "SW1") (pin "1") (pinfunction "+_1") (pintype "passive"))
      (node (ref "SW2") (pin "1") (pinfunction "+_1") (pintype "passive"))
    )
    (net (code "24") (name "Net-(INSEL_CTRLB-S)") (class "Default")
      (node (ref "INSEL_CTRL") (pin "2") (pinfunction "S_2") (pintype "passive"))
      (node (ref "R21") (pin "1") (pinfunction "1_1") (pintype "passive"))
    )
    (net (code "25") (name "Net-(INSEL_CTRLC-S)") (class "Default")
      (node (ref "INSEL_CTRL") (pin "3") (pinfunction "S_3") (pintype "passive"))
      (node (ref "Q1") (pin "3") (pinfunction "E_3") (pintype "passive"))
    )
    (net (code "26") (name "Net-(INSEL_IN_AA-S)") (class "Default")
      (node (ref "INSEL_IN_A") (pin "1") (pinfunction "S_1") (pintype "passive"))
      (node (ref "SW2") (pin "3") (pinfunction "P_3") (pintype "passive"))
    )
    (net (code "27") (name "Net-(INSEL_IN_AC-S)") (class "Default")
      (node (ref "INSEL_IN_A") (pin "3") (pinfunction "S_3") (pintype "passive"))
      (node (ref "SW2") (pin "6") (pinfunction "P_6") (pintype "passive"))
    )
    (net (code "28") (name "Net-(INSEL_IN_BA-S)") (class "Default")
      (node (ref "INSEL_IN_B") (pin "1") (pinfunction "S_1") (pintype "passive"))
      (node (ref "SW1") (pin "3") (pinfunction "P_3") (pintype "passive"))
    )
    (net (code "29") (name "Net-(INSEL_IN_BC-S)") (class "Default")
      (node (ref "INSEL_IN_B") (pin "3") (pinfunction "S_3") (pintype "passive"))
      (node (ref "SW1") (pin "6") (pinfunction "P_6") (pintype "passive"))
    )
    (net (code "30") (name "Net-(INSEL_OUTA-S)") (class "Default")
      (node (ref "INSEL_OUT") (pin "1") (pinfunction "S_1") (pintype "passive"))
      (node (ref "SW1") (pin "4") (pinfunction "S_4") (pintype "passive"))
      (node (ref "SW2") (pin "2") (pinfunction "O_2") (pintype "passive"))
    )
    (net (code "31") (name "Net-(INSEL_OUTC-S)") (class "Default")
      (node (ref "INSEL_OUT") (pin "3") (pinfunction "S_3") (pintype "passive"))
      (node (ref "SW1") (pin "5") (pinfunction "S_5") (pintype "passive"))
      (node (ref "SW2") (pin "7") (pinfunction "O_7") (pintype "passive"))
    )
    (net (code "32") (name "Net-(K1B-S)") (class "Default")
      (node (ref "JP1") (pin "TIP") (pinfunction "TIP_TIP") (pintype "bidirectional"))
      (node (ref "K1") (pin "S1") (pinfunction "S_S1") (pintype "passive"))
    )
    (net (code "33") (name "Net-(K1C-S)") (class "Default")
      (node (ref "JP1") (pin "RING") (pinfunction "RING_RING") (pintype "bidirectional"))
      (node (ref "K1") (pin "S2") (pinfunction "S_S2") (pintype "passive"))
    )
    (net (code "34") (name "Net-(PSU_AMP_OUTB-S)") (class "Default")
      (node (ref "F1") (pin "2") (pinfunction "2_2") (pintype "passive"))
      (node (ref "PSU_AMP_OUT") (pin "2") (pinfunction "S_2") (pintype "passive"))
      (node (ref "TP_AMPPWR") (pin "TP") (pinfunction "TP_TP") (pintype "input"))
    )
    (net (code "35") (name "Net-(PSU_SWA-S)") (class "Default")
      (node (ref "D4") (pin "A") (pinfunction "A_A") (pintype "passive"))
      (node (ref "PSU_SW") (pin "1") (pinfunction "S_1") (pintype "passive"))
    )
    (net (code "36") (name "Net-(PSU_SWB-S)") (class "Default")
      (node (ref "J2") (pin "3") (pinfunction "3_3") (pintype "passive"))
      (node (ref "PSU_SW") (pin "2") (pinfunction "S_2") (pintype "passive"))
    )
    (net (code "37") (name "Net-(Q1-B)") (class "Default")
      (node (ref "Q1") (pin "2") (pinfunction "B_2") (pintype "passive"))
      (node (ref "R21") (pin "2") (pinfunction "2_2") (pintype "passive"))
    )
    (net (code "38") (name "Net-(Q2-B)") (class "Default")
      (node (ref "Q2") (pin "2") (pinfunction "B_2") (pintype "passive"))
      (node (ref "R18") (pin "2") (pinfunction "2_2") (pintype "passive"))
    )
    (net (code "39") (name "Net-(Q3-PadG)") (class "Default")
      (node (ref "Q3") (pin "G") (pinfunction "G_G") (pintype "passive"))
      (node (ref "R5") (pin "S") (pinfunction "S_S") (pintype "passive"))
    )
    (net (code "40") (name "Net-(Q4-PadG)") (class "Default")
      (node (ref "Q4") (pin "G") (pinfunction "G_G") (pintype "passive"))
      (node (ref "R6") (pin "S") (pinfunction "S_S") (pintype "passive"))
    )
    (net (code "41") (name "Net-(R13-1)") (class "Default")
      (node (ref "R13") (pin "P$1") (pinfunction "1_P$1") (pintype "passive"))
      (node (ref "R14") (pin "E") (pinfunction "E_E") (pintype "passive"))
    )
    (net (code "42") (name "Net-(R15-1)") (class "Default")
      (node (ref "R15") (pin "P$1") (pinfunction "1_P$1") (pintype "passive"))
      (node (ref "SW2") (pin "4") (pinfunction "S_4") (pintype "passive"))
    )
    (net (code "43") (name "Net-(R16-1)") (class "Default")
      (node (ref "R16") (pin "P$1") (pinfunction "1_P$1") (pintype "passive"))
      (node (ref "SW1") (pin "2") (pinfunction "O_2") (pintype "passive"))
    )
    (net (code "44") (name "Net-(R17-1)") (class "Default")
      (node (ref "R17") (pin "P$1") (pinfunction "1_P$1") (pintype "passive"))
      (node (ref "SW2") (pin "5") (pinfunction "S_5") (pintype "passive"))
    )
    (net (code "45") (name "Net-(R20-1)") (class "Default")
      (node (ref "R20") (pin "P$1") (pinfunction "1_P$1") (pintype "passive"))
      (node (ref "SW1") (pin "7") (pinfunction "O_7") (pintype "passive"))
    )
    (net (code "46") (name "Net-(RCA_INA-S)") (class "Default")
      (node (ref "RCA_IN") (pin "1") (pinfunction "S_1") (pintype "passive"))
      (node (ref "X3") (pin "T") (pinfunction "T_T") (pintype "passive"))
    )
    (net (code "47") (name "Net-(RCA_INB-S)") (class "Default")
      (node (ref "RCA_IN") (pin "2") (pinfunction "S_2") (pintype "passive"))
      (node (ref "X2") (pin "S") (pinfunction "S_S") (pintype "passive"))
      (node (ref "X3") (pin "S") (pinfunction "S_S") (pintype "passive"))
    )
    (net (code "48") (name "Net-(RCA_INC-S)") (class "Default")
      (node (ref "RCA_IN") (pin "3") (pinfunction "S_3") (pintype "passive"))
      (node (ref "X2") (pin "T") (pinfunction "T_T") (pintype "passive"))
    )
    (net (code "49") (name "Net-(TUBE_LIGHT1A-S)") (class "Default")
      (node (ref "LED2") (pin "A") (pinfunction "A_A") (pintype "passive"))
      (node (ref "TUBE_LIGHT1") (pin "1") (pinfunction "S_1") (pintype "passive"))
    )
    (net (code "50") (name "Net-(TUBE_LIGHTA-S)") (class "Default")
      (node (ref "LED1") (pin "A") (pinfunction "A_A") (pintype "passive"))
      (node (ref "R11") (pin "2") (pinfunction "2_2") (pintype "passive"))
      (node (ref "TUBE_LIGHT") (pin "1") (pinfunction "S_1") (pintype "passive"))
    )
    (net (code "51") (name "Net-(U1-PB0(MOSI))") (class "Default")
      (node (ref "R11") (pin "1") (pinfunction "1_1") (pintype "passive"))
      (node (ref "U1") (pin "5") (pinfunction "PB0(MOSI)_5") (pintype "bidirectional"))
    )
    (net (code "52") (name "Net-(U1-PB1(MISO))") (class "Default")
      (node (ref "R18") (pin "1") (pinfunction "1_1") (pintype "passive"))
      (node (ref "U1") (pin "6") (pinfunction "PB1(MISO)_6") (pintype "bidirectional"))
    )
    (net (code "53") (name "Net-(U1-PB2(SCK{slash}ADC1))") (class "Default")
      (node (ref "JP2") (pin "1") (pinfunction "1_1") (pintype "passive"))
      (node (ref "U1") (pin "7") (pinfunction "PB2(SCK/ADC1)_7") (pintype "bidirectional"))
    )
    (net (code "54") (name "Net-(U1-PB3(ADC3))") (class "Default")
      (node (ref "JP3") (pin "1") (pinfunction "1_1") (pintype "passive"))
      (node (ref "U1") (pin "2") (pinfunction "PB3(ADC3)_2") (pintype "bidirectional"))
    )
    (net (code "55") (name "Net-(U1-PB4(ADC2))") (class "Default")
      (node (ref "JP3") (pin "2") (pinfunction "2_2") (pintype "passive"))
      (node (ref "U1") (pin "3") (pinfunction "PB4(ADC2)_3") (pintype "bidirectional"))
    )
    (net (code "56") (name "Net-(U1-PB5(NRES))") (class "Default")
      (node (ref "R19") (pin "1") (pinfunction "1_1") (pintype "passive"))
      (node (ref "U1") (pin "1") (pinfunction "PB5(NRES)_1") (pintype "bidirectional"))
    )
    (net (code "57") (name "Net-(USB_INA-S)") (class "Default")
      (node (ref "USB_IN") (pin "1") (pinfunction "S_1") (pintype "passive"))
      (node (ref "X1") (pin "4") (pinfunction "4_4") (pintype "passive"))
      (node (ref "X1") (pin "S1") (pinfunction "S1_S1") (pintype "passive"))
      (node (ref "X1") (pin "S2") (pinfunction "S2_S2") (pintype "passive"))
    )
    (net (code "58") (name "Net-(USB_INB-S)") (class "Default")
      (node (ref "USB_IN") (pin "2") (pinfunction "S_2") (pintype "passive"))
      (node (ref "X1") (pin "1") (pinfunction "1_1") (pintype "passive"))
    )
    (net (code "59") (name "Net-(USB_INC-S)") (class "Default")
      (node (ref "USB_IN") (pin "3") (pinfunction "S_3") (pintype "passive"))
      (node (ref "X1") (pin "2") (pinfunction "2_2") (pintype "passive"))
    )
    (net (code "60") (name "Net-(USB_IND-S)") (class "Default")
      (node (ref "USB_IN") (pin "4") (pinfunction "S_4") (pintype "passive"))
      (node (ref "X1") (pin "3") (pinfunction "3_3") (pintype "passive"))
    )
    (net (code "61") (name "Net-(V1B-TA)") (class "Default")
      (node (ref "R5") (pin "A") (pinfunction "A_A") (pintype "passive"))
      (node (ref "V1") (pin "1") (pinfunction "TA_1") (pintype "passive"))
    )
    (net (code "62") (name "Net-(V1B-TG)") (class "Default")
      (node (ref "C5") (pin "2") (pinfunction "2_2") (pintype "passive"))
      (node (ref "R1") (pin "2") (pinfunction "2_2") (pintype "passive"))
      (node (ref "V1") (pin "2") (pinfunction "TG_2") (pintype "passive"))
    )
    (net (code "63") (name "Net-(V1B-TK)") (class "Default")
      (node (ref "C1") (pin "+") (pinfunction "+_+") (pintype "passive"))
      (node (ref "R2") (pin "2") (pinfunction "2_2") (pintype "passive"))
      (node (ref "V1") (pin "3") (pinfunction "TK_3") (pintype "passive"))
    )
    (net (code "64") (name "Net-(V1C-TA)") (class "Default")
      (node (ref "R6") (pin "A") (pinfunction "A_A") (pintype "passive"))
      (node (ref "V1") (pin "6") (pinfunction "TA_6") (pintype "passive"))
    )
    (net (code "65") (name "Net-(V1C-TG)") (class "Default")
      (node (ref "C6") (pin "2") (pinfunction "2_2") (pintype "passive"))
      (node (ref "R7") (pin "2") (pinfunction "2_2") (pintype "passive"))
      (node (ref "V1") (pin "7") (pinfunction "TG_7") (pintype "passive"))
    )
    (net (code "66") (name "Net-(V1C-TK)") (class "Default")
      (node (ref "C2") (pin "+") (pinfunction "+_+") (pintype "passive"))
      (node (ref "R8") (pin "2") (pinfunction "2_2") (pintype "passive"))
      (node (ref "V1") (pin "8") (pinfunction "TK_8") (pintype "passive"))
    )
    (net (code "67") (name "Net-(VOLUMEA-1)") (class "Default")
      (node (ref "R22") (pin "1") (pinfunction "1_1") (pintype "passive"))
      (node (ref "R23") (pin "1") (pinfunction "1_1") (pintype "passive"))
      (node (ref "VOLUME") (pin "G1") (pinfunction "1_G1") (pintype "passive"))
      (node (ref "VOLUME") (pin "G2") (pinfunction "1_G2") (pintype "passive"))
      (node (ref "VOL_IN") (pin "2") (pinfunction "S_2") (pintype "passive"))
      (node (ref "VOL_OUT") (pin "2") (pinfunction "S_2") (pintype "passive"))
    )
    (net (code "68") (name "Net-(VOLUMEA-2)") (class "Default")
      (node (ref "R22") (pin "2") (pinfunction "2_2") (pintype "passive"))
      (node (ref "VOLUME") (pin "O1") (pinfunction "2_O1") (pintype "passive"))
      (node (ref "VOL_OUT") (pin "1") (pinfunction "S_1") (pintype "passive"))
    )
    (net (code "69") (name "Net-(VOLUMEA-3)") (class "Default")
      (node (ref "VOLUME") (pin "I1") (pinfunction "3_I1") (pintype "passive"))
      (node (ref "VOL_IN") (pin "1") (pinfunction "S_1") (pintype "passive"))
    )
    (net (code "70") (name "Net-(VOLUMEB-2)") (class "Default")
      (node (ref "R23") (pin "2") (pinfunction "2_2") (pintype "passive"))
      (node (ref "VOLUME") (pin "O2") (pinfunction "2_O2") (pintype "passive"))
      (node (ref "VOL_OUT") (pin "3") (pinfunction "S_3") (pintype "passive"))
    )
    (net (code "71") (name "Net-(VOLUMEB-3)") (class "Default")
      (node (ref "VOLUME") (pin "I2") (pinfunction "3_I2") (pintype "passive"))
      (node (ref "VOL_IN") (pin "3") (pinfunction "S_3") (pintype "passive"))
    )
    (net (code "72") (name "OUTPUT_L") (class "Default")
      (node (ref "C3") (pin "-") (pinfunction "-_-") (pintype "passive"))
      (node (ref "OUTPUT") (pin "1") (pinfunction "S_1") (pintype "passive"))
      (node (ref "R4") (pin "2") (pinfunction "2_2") (pintype "passive"))
    )
    (net (code "73") (name "OUTPUT_R") (class "Default")
      (node (ref "C4") (pin "-") (pinfunction "-_-") (pintype "passive"))
      (node (ref "OUTPUT") (pin "3") (pinfunction "S_3") (pintype "passive"))
      (node (ref "R10") (pin "2") (pinfunction "2_2") (pintype "passive"))
    )
    (net (code "74") (name "VCC") (class "Default")
      (node (ref "C10") (pin "1") (pinfunction "1_1") (pintype "passive"))
      (node (ref "C11") (pin "1") (pinfunction "1_1") (pintype "passive"))
      (node (ref "C16") (pin "1") (pinfunction "1_1") (pintype "passive"))
      (node (ref "C7") (pin "+") (pinfunction "+_+") (pintype "passive"))
      (node (ref "C8") (pin "+") (pinfunction "+_+") (pintype "passive"))
      (node (ref "D1") (pin "C") (pinfunction "C_C") (pintype "passive"))
      (node (ref "D4") (pin "C") (pinfunction "C_C") (pintype "passive"))
      (node (ref "D5") (pin "C") (pinfunction "C_C") (pintype "passive"))
      (node (ref "DLY_PWR1") (pin "1") (pinfunction "S_1") (pintype "passive"))
      (node (ref "FILAMENT_PWR") (pin "3") (pinfunction "S_3") (pintype "passive"))
      (node (ref "IC3") (pin "3") (pinfunction "IN_3") (pintype "input"))
      (node (ref "IC4") (pin "1") (pinfunction "VI_1") (pintype "input"))
      (node (ref "IC5") (pin "1") (pinfunction "VI_1") (pintype "input"))
      (node (ref "PSU_AUX") (pin "2") (pinfunction "S_2") (pintype "passive"))
      (node (ref "PSU_AUX1") (pin "2") (pinfunction "S_2") (pintype "passive"))
      (node (ref "PSU_AUX2") (pin "2") (pinfunction "S_2") (pintype "passive"))
      (node (ref "V1") (pin "5") (pinfunction "H3_5") (pintype "passive"))
    )
    (net (code "75") (name "unconnected-(J2-Pad2)") (class "Default")
      (node (ref "J2") (pin "2") (pinfunction "2_2") (pintype "passive"))
    )
    (net (code "76") (name "unconnected-(JP1-EARTH-NORM-PadSLEEVE-NORM)") (class "Default")
      (node (ref "JP1") (pin "SLEEVE-NORM") (pinfunction "EARTH-NORM_SLEEVE-NORM") (pintype "bidirectional"))
    )
    (net (code "77") (name "unconnected-(JP1-PadRING-NORM)") (class "Default")
      (node (ref "JP1") (pin "RING-NORM") (pinfunction "RING-NORM_RING-NORM") (pintype "bidirectional"))
    )
    (net (code "78") (name "unconnected-(JP1-PadTIP-NORM)") (class "Default")
      (node (ref "JP1") (pin "TIP-NORM") (pinfunction "TIP-NORM_TIP-NORM") (pintype "bidirectional"))
    )
    (net (code "79") (name "unconnected-(K1B-O-PadO1)") (class "Default")
      (node (ref "K1") (pin "O1") (pinfunction "O_O1") (pintype "passive"))
    )
    (net (code "80") (name "unconnected-(K1C-O-PadO2)") (class "Default")
      (node (ref "K1") (pin "O2") (pinfunction "O_O2") (pintype "passive"))
    )
  )
)
